# G-SENSOR.net
KiCad netlist of a schematic drawn in Altium Designer
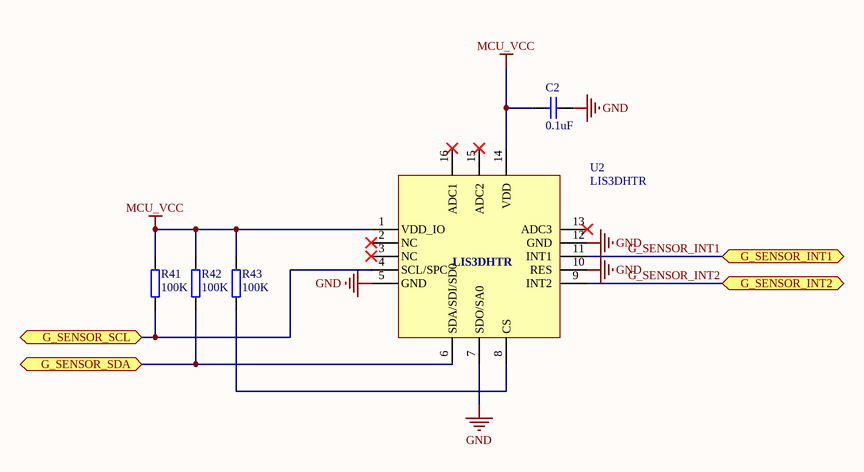
[diagram p0: G-SENSOR.SchDoc]

(export (version "E")
  (design (tool "Eeschema 10.0.6"))
  (components
    (comp (ref "C2")
      (value "0.1uF")
      (footprint "0603C")
      (description "Capacitor")
      (fields (field (name "PUBLISHER") "Altium Limited"))
      (libsource (lib "Calf") (part "Cap"))
    )
    (comp (ref "R41") (value "100K") (footprint "0603R") (libsource (lib "dtu02") (part "RES2A")))
    (comp (ref "R42") (value "100K") (footprint "0603R") (libsource (lib "dtu02") (part "RES2A")))
    (comp (ref "R43") (value "100K") (footprint "0603R") (libsource (lib "dtu02") (part "RES2A")))
    (comp (ref "U2")
      (value "LIS3DHTR")
      (footprint "LC-LGA-16_3x3mm")
      (libsource (lib "GBOX_V2") (part "LIS3DHTR"))
    )
  )
  (nets
    (net (code "1") (name "/G_SENSOR_INT1") (class "Default")
      (node (ref "U2") (pin "11") (pinfunction "INT1_11") (pintype "passive"))
    )
    (net (code "2") (name "/G_SENSOR_INT2") (class "Default")
      (node (ref "U2") (pin "9") (pinfunction "INT2_9") (pintype "passive"))
    )
    (net (code "3") (name "/G_SENSOR_SCL") (class "Default")
      (node (ref "R41") (pin "2") (pintype "passive"))
      (node (ref "U2") (pin "4") (pinfunction "SCL/SPC_4") (pintype "passive"))
    )
    (net (code "4") (name "/G_SENSOR_SDA") (class "Default")
      (node (ref "R42") (pin "2") (pintype "passive"))
      (node (ref "U2") (pin "6") (pinfunction "SDA/SDI/SD0_6") (pintype "passive"))
    )
    (net (code "5") (name "GND") (class "Default")
      (node (ref "C2") (pin "1") (pinfunction "1_1") (pintype "passive"))
      (node (ref "U2") (pin "10") (pinfunction "RES_10") (pintype "passive"))
      (node (ref "U2") (pin "12") (pinfunction "GND_12") (pintype "passive"))
      (node (ref "U2") (pin "5") (pinfunction "GND_5") (pintype "passive"))
      (node (ref "U2") (pin "7") (pinfunction "SDO/SA0_7") (pintype "passive"))
    )
    (net (code "6") (name "MCU_VCC") (class "Default")
      (node (ref "C2") (pin "2") (pinfunction "2_2") (pintype "passive"))
      (node (ref "R41") (pin "1") (pintype "passive"))
      (node (ref "R42") (pin "1") (pintype "passive"))
      (node (ref "R43") (pin "1") (pintype "passive"))
      (node (ref "U2") (pin "1") (pinfunction "VDD_IO_1") (pintype "passive"))
      (node (ref "U2") (pin "14") (pinfunction "VDD_14") (pintype "passive"))
    )
    (net (code "7") (name "Net-(U2-CS)") (class "Default")
      (node (ref "R43") (pin "2") (pintype "passive"))
      (node (ref "U2") (pin "8") (pinfunction "CS_8") (pintype "passive"))
    )
    (net (code "8") (name "unconnected-(U2-ADC1-Pad16)") (class "Default")
      (node (ref "U2") (pin "16") (pinfunction "ADC1_16") (pintype "passive+no_connect"))
    )
    (net (code "9") (name "unconnected-(U2-ADC2-Pad15)") (class "Default")
      (node (ref "U2") (pin "15") (pinfunction "ADC2_15") (pintype "passive+no_connect"))
    )
    (net (code "10") (name "unconnected-(U2-ADC3-Pad13)") (class "Default")
      (node (ref "U2") (pin "13") (pinfunction "ADC3_13") (pintype "passive+no_connect"))
    )
    (net (code "11") (name "unconnected-(U2-NC-Pad2)") (class "Default")
      (node (ref "U2") (pin "2") (pinfunction "NC_2") (pintype "passive+no_connect"))
    )
    (net (code "12") (name "unconnected-(U2-NC-Pad3)") (class "Default")
      (node (ref "U2") (pin "3") (pinfunction "NC_3") (pintype "passive+no_connect"))
    )
  )
)
